# SparkFun_Load_Sensor_Combinator.net
KiCad netlist of a schematic drawn in EAGLE
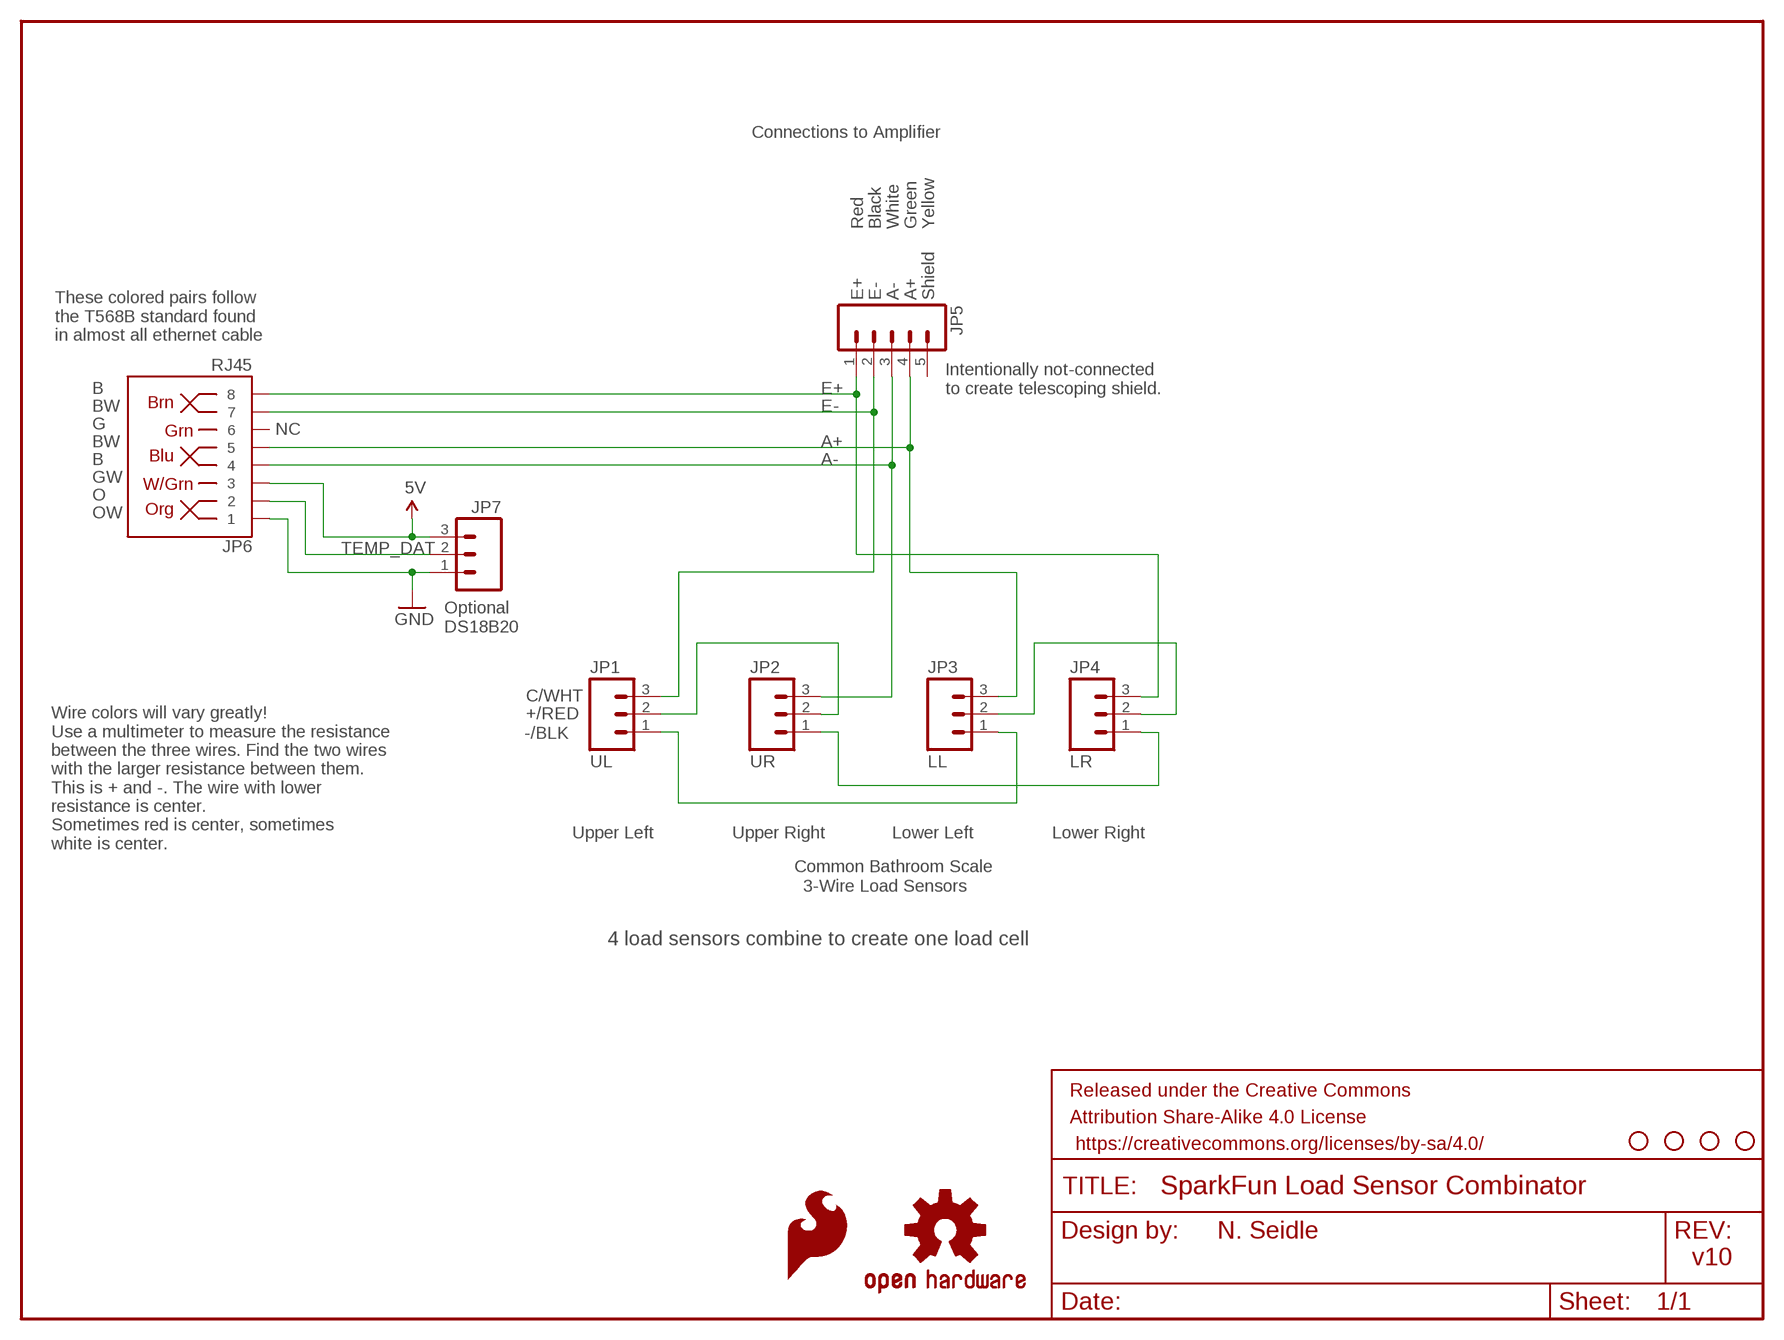
[diagram p0: schematic, sheet 1]

(export (version "E")
  (design (tool "Eeschema 10.0.6"))
  (components
    (comp (ref "FRAME1")
      (value "FRAME-LETTER")
      (footprint "eagle-import:CREATIVE_COMMONS")
      (fields (field (name "DESIGNER") "N. Seidle") (field (name "VERSION") "v02"))
      (libsource (lib "eagle-import") (part "FRAME-LETTER"))
    )
    (comp (ref "JP1")
      (value "UL")
      (footprint "eagle-import:1X03")
      (libsource (lib "eagle-import") (part "M03PTH"))
    )
    (comp (ref "JP2")
      (value "UR")
      (footprint "eagle-import:1X03")
      (libsource (lib "eagle-import") (part "M03PTH"))
    )
    (comp (ref "JP3")
      (value "LL")
      (footprint "eagle-import:1X03")
      (libsource (lib "eagle-import") (part "M03PTH"))
    )
    (comp (ref "JP4")
      (value "LR")
      (footprint "eagle-import:1X03")
      (libsource (lib "eagle-import") (part "M03PTH"))
    )
    (comp (ref "JP5")
      (value "M05PTH")
      (footprint "eagle-import:1X05")
      (libsource (lib "eagle-import") (part "M05PTH"))
    )
    (comp (ref "JP6")
      (value "RJ45")
      (footprint "eagle-import:RJ45-8")
      (libsource (lib "eagle-import") (part "RJ45-8PTH"))
    )
    (comp (ref "JP7")
      (value "M03PTH")
      (footprint "eagle-import:1X03")
      (libsource (lib "eagle-import") (part "M03PTH"))
    )
    (comp (ref "LOGO3")
      (value "SFE_LOGO_FLAME.1_INCH")
      (footprint "eagle-import:SFE_LOGO_FLAME_.1")
      (libsource (lib "eagle-import") (part "SFE_LOGO_FLAME.1_INCH"))
    )
    (comp (ref "STANDOFF1")
      (value "STAND-OFF")
      (footprint "eagle-import:STAND-OFF")
      (libsource (lib "eagle-import") (part "STAND-OFF"))
    )
    (comp (ref "STANDOFF2")
      (value "STAND-OFF")
      (footprint "eagle-import:STAND-OFF")
      (libsource (lib "eagle-import") (part "STAND-OFF"))
    )
    (comp (ref "STANDOFF3")
      (value "STAND-OFF")
      (footprint "eagle-import:STAND-OFF")
      (libsource (lib "eagle-import") (part "STAND-OFF"))
    )
    (comp (ref "STANDOFF4")
      (value "STAND-OFF")
      (footprint "eagle-import:STAND-OFF")
      (libsource (lib "eagle-import") (part "STAND-OFF"))
    )
    (comp (ref "U$7")
      (value "OSHW-LOGOS")
      (footprint "eagle-import:OSHW-LOGO-S")
      (libsource (lib "eagle-import") (part "OSHW-LOGOS"))
    )
  )
  (nets
    (net (code "1") (name "/A+") (class "Default")
      (node (ref "JP3") (pin "3") (pinfunction "3_3") (pintype "passive"))
      (node (ref "JP5") (pin "4") (pinfunction "4_4") (pintype "passive"))
      (node (ref "JP6") (pin "5") (pinfunction "5_5") (pintype "bidirectional"))
    )
    (net (code "2") (name "/A-") (class "Default")
      (node (ref "JP2") (pin "3") (pinfunction "3_3") (pintype "passive"))
      (node (ref "JP5") (pin "3") (pinfunction "3_3") (pintype "passive"))
      (node (ref "JP6") (pin "4") (pinfunction "4_4") (pintype "bidirectional"))
    )
    (net (code "3") (name "/E+") (class "Default")
      (node (ref "JP4") (pin "3") (pinfunction "3_3") (pintype "passive"))
      (node (ref "JP5") (pin "1") (pinfunction "1_1") (pintype "passive"))
      (node (ref "JP6") (pin "8") (pinfunction "8_8") (pintype "bidirectional"))
    )
    (net (code "4") (name "/E-") (class "Default")
      (node (ref "JP1") (pin "3") (pinfunction "3_3") (pintype "passive"))
      (node (ref "JP5") (pin "2") (pinfunction "2_2") (pintype "passive"))
      (node (ref "JP6") (pin "7") (pinfunction "7_7") (pintype "bidirectional"))
    )
    (net (code "5") (name "/TEMP_DAT") (class "Default")
      (node (ref "JP6") (pin "2") (pinfunction "2_2") (pintype "bidirectional"))
      (node (ref "JP7") (pin "2") (pinfunction "2_2") (pintype "passive"))
    )
    (net (code "6") (name "5V") (class "Default")
      (node (ref "JP6") (pin "3") (pinfunction "3_3") (pintype "bidirectional"))
      (node (ref "JP7") (pin "3") (pinfunction "3_3") (pintype "passive"))
    )
    (net (code "7") (name "GND") (class "Default")
      (node (ref "JP6") (pin "1") (pinfunction "1_1") (pintype "bidirectional"))
      (node (ref "JP7") (pin "1") (pinfunction "1_1") (pintype "passive"))
    )
    (net (code "8") (name "Net-(JP1-Pad1)") (class "Default")
      (node (ref "JP1") (pin "1") (pinfunction "1_1") (pintype "passive"))
      (node (ref "JP3") (pin "1") (pinfunction "1_1") (pintype "passive"))
    )
    (net (code "9") (name "Net-(JP1-Pad2)") (class "Default")
      (node (ref "JP1") (pin "2") (pinfunction "2_2") (pintype "passive"))
      (node (ref "JP2") (pin "2") (pinfunction "2_2") (pintype "passive"))
    )
    (net (code "10") (name "Net-(JP2-Pad1)") (class "Default")
      (node (ref "JP2") (pin "1") (pinfunction "1_1") (pintype "passive"))
      (node (ref "JP4") (pin "1") (pinfunction "1_1") (pintype "passive"))
    )
    (net (code "11") (name "Net-(JP3-Pad2)") (class "Default")
      (node (ref "JP3") (pin "2") (pinfunction "2_2") (pintype "passive"))
      (node (ref "JP4") (pin "2") (pinfunction "2_2") (pintype "passive"))
    )
    (net (code "12") (name "unconnected-(JP5-Pad5)") (class "Default")
      (node (ref "JP5") (pin "5") (pinfunction "5_5") (pintype "passive"))
    )
    (net (code "13") (name "unconnected-(JP6-Pad6)") (class "Default")
      (node (ref "JP6") (pin "6") (pinfunction "6_6") (pintype "bidirectional"))
    )
  )
)
